# Sheet1.net
KiCad netlist of a schematic drawn in Altium Designer
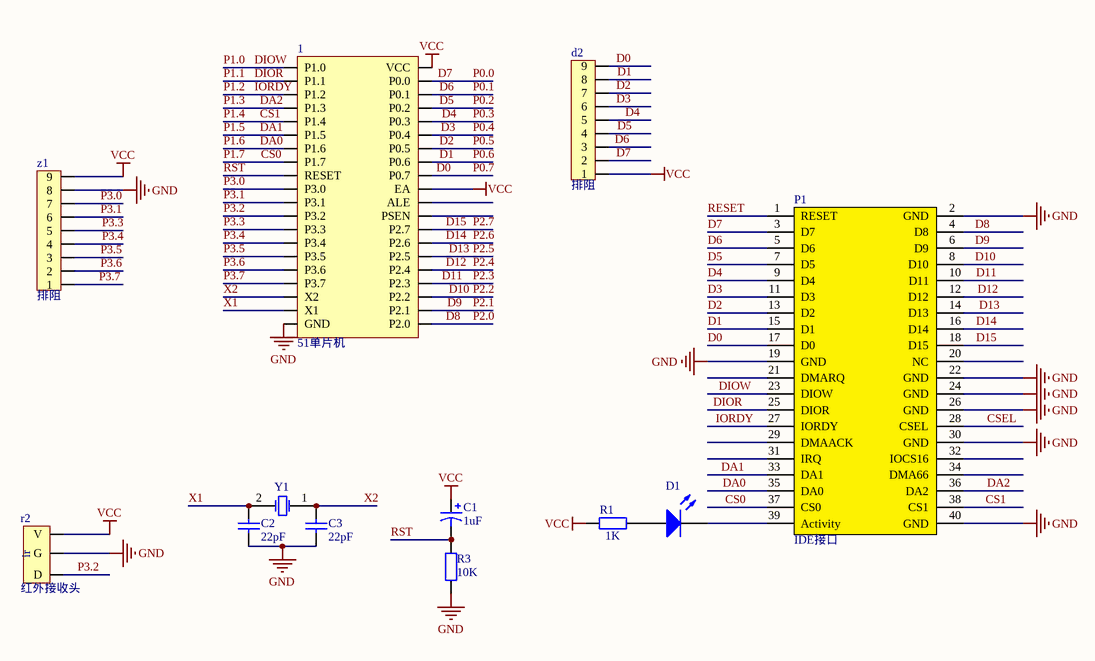
[diagram p0: Sheet1.SchDoc]

(export (version "E")
  (design (tool "Eeschema 10.0.6"))
  (components
    (comp (ref "1") (value "51单片机") (footprint "51单片机") (libsource (lib "原理图库") (part "51单片机")))
    (comp (ref "C1")
      (value "1uF")
      (footprint "电解电容")
      (description "Polarized Capacitor (Radial)")
      (fields (field (name "Comment") "Cap Pol1") (field (name "PUBLISHER") "Altium Limited"))
      (libsource (lib "系统自带集成库") (part "Cap Pol1"))
    )
    (comp (ref "C2")
      (value "22pF")
      (footprint "无极电容")
      (description "Capacitor")
      (fields (field (name "Comment") "Cap") (field (name "PUBLISHER") "Altium Limited"))
      (libsource (lib "系统自带集成库") (part "Cap"))
    )
    (comp (ref "C3")
      (value "22pF")
      (footprint "无极电容")
      (description "Capacitor")
      (fields (field (name "Comment") "Cap") (field (name "PUBLISHER") "Altium Limited"))
      (libsource (lib "系统自带集成库") (part "Cap"))
    )
    (comp (ref "D1")
      (value "LED0")
      (footprint "LED")
      (description "Typical INFRARED GaAs LED")
      (fields (field (name "PUBLISHER") "Altium Limited"))
      (libsource (lib "Miscellaneous Devices") (part "LED0"))
    )
    (comp (ref "d2") (value "排阻") (footprint "排阻") (libsource (lib "原理图库") (part "排阻")))
    (comp (ref "P1") (value "IDE接口") (footprint "IDE接口封装40PIN") (libsource (lib "原理图库") (part "IDE接口")))
    (comp (ref "R1")
      (value "1K")
      (footprint "电阻")
      (description "Resistor")
      (fields (field (name "Comment") "Res2") (field (name "PUBLISHER") "Altium Limited"))
      (libsource (lib "Miscellaneous Devices") (part "Res2"))
    )
    (comp (ref "r2") (value "红外接收头") (footprint "IR红外接收头") (libsource (lib "原理图库") (part "红外接收头")))
    (comp (ref "R3")
      (value "10K")
      (footprint "电阻")
      (description "Resistor")
      (fields (field (name "Comment") "Res2") (field (name "PUBLISHER") "Altium Limited"))
      (libsource (lib "系统自带集成库") (part "Res2"))
    )
    (comp (ref "Y1")
      (value "XTAL")
      (footprint "晶振")
      (description "Crystal Oscillator")
      (fields (field (name "PUBLISHER") "Altium Limited"))
      (libsource (lib "系统自带集成库") (part "XTAL"))
    )
    (comp (ref "z1") (value "排阻") (footprint "排阻") (libsource (lib "原理图库") (part "排阻")))
  )
  (nets
    (net (code "1") (name "/CS0") (class "Default")
      (node (ref "1") (pin "8") (pinfunction "P1.7_8") (pintype "passive"))
      (node (ref "P1") (pin "37") (pinfunction "CS0_37") (pintype "passive"))
    )
    (net (code "2") (name "/CS1") (class "Default")
      (node (ref "1") (pin "5") (pinfunction "P1.4_5") (pintype "passive"))
      (node (ref "P1") (pin "38") (pinfunction "CS1_38") (pintype "passive"))
    )
    (net (code "3") (name "/CSEL") (class "Default")
      (node (ref "P1") (pin "28") (pinfunction "CSEL_28") (pintype "passive"))
    )
    (net (code "4") (name "/D0") (class "Default")
      (node (ref "1") (pin "32") (pinfunction "P0.7_32") (pintype "passive"))
      (node (ref "P1") (pin "17") (pinfunction "D0_17") (pintype "passive"))
      (node (ref "d2") (pin "9") (pinfunction "9_9") (pintype "passive"))
    )
    (net (code "5") (name "/D1") (class "Default")
      (node (ref "1") (pin "33") (pinfunction "P0.6_33") (pintype "passive"))
      (node (ref "P1") (pin "15") (pinfunction "D1_15") (pintype "passive"))
      (node (ref "d2") (pin "8") (pinfunction "8_8") (pintype "passive"))
    )
    (net (code "6") (name "/D2") (class "Default")
      (node (ref "1") (pin "34") (pinfunction "P0.5_34") (pintype "passive"))
      (node (ref "P1") (pin "13") (pinfunction "D2_13") (pintype "passive"))
      (node (ref "d2") (pin "7") (pinfunction "7_7") (pintype "passive"))
    )
    (net (code "7") (name "/D3") (class "Default")
      (node (ref "1") (pin "35") (pinfunction "P0.4_35") (pintype "passive"))
      (node (ref "P1") (pin "11") (pinfunction "D3_11") (pintype "passive"))
      (node (ref "d2") (pin "6") (pinfunction "6_6") (pintype "passive"))
    )
    (net (code "8") (name "/D4") (class "Default")
      (node (ref "1") (pin "36") (pinfunction "P0.3_36") (pintype "passive"))
      (node (ref "P1") (pin "9") (pinfunction "D4_9") (pintype "passive"))
      (node (ref "d2") (pin "5") (pinfunction "5_5") (pintype "passive"))
    )
    (net (code "9") (name "/D5") (class "Default")
      (node (ref "1") (pin "37") (pinfunction "P0.2_37") (pintype "passive"))
      (node (ref "P1") (pin "7") (pinfunction "D5_7") (pintype "passive"))
      (node (ref "d2") (pin "4") (pinfunction "4_4") (pintype "passive"))
    )
    (net (code "10") (name "/D6") (class "Default")
      (node (ref "1") (pin "38") (pinfunction "P0.1_38") (pintype "passive"))
      (node (ref "P1") (pin "5") (pinfunction "D6_5") (pintype "passive"))
      (node (ref "d2") (pin "3") (pinfunction "3_3") (pintype "passive"))
    )
    (net (code "11") (name "/D7") (class "Default")
      (node (ref "1") (pin "39") (pinfunction "P0.0_39") (pintype "passive"))
      (node (ref "P1") (pin "3") (pinfunction "D7_3") (pintype "passive"))
      (node (ref "d2") (pin "2") (pinfunction "2_2") (pintype "passive"))
    )
    (net (code "12") (name "/D8") (class "Default")
      (node (ref "1") (pin "21") (pinfunction "P2.0_21") (pintype "passive"))
      (node (ref "P1") (pin "4") (pinfunction "D8_4") (pintype "passive"))
    )
    (net (code "13") (name "/D9") (class "Default")
      (node (ref "1") (pin "22") (pinfunction "P2.1_22") (pintype "passive"))
      (node (ref "P1") (pin "6") (pinfunction "D9_6") (pintype "passive"))
    )
    (net (code "14") (name "/D10") (class "Default")
      (node (ref "1") (pin "23") (pinfunction "P2.2_23") (pintype "passive"))
      (node (ref "P1") (pin "8") (pinfunction "D10_8") (pintype "passive"))
    )
    (net (code "15") (name "/D11") (class "Default")
      (node (ref "1") (pin "24") (pinfunction "P2.3_24") (pintype "passive"))
      (node (ref "P1") (pin "10") (pinfunction "D11_10") (pintype "passive"))
    )
    (net (code "16") (name "/D12") (class "Default")
      (node (ref "1") (pin "25") (pinfunction "P2.4_25") (pintype "passive"))
      (node (ref "P1") (pin "12") (pinfunction "D12_12") (pintype "passive"))
    )
    (net (code "17") (name "/D13") (class "Default")
      (node (ref "1") (pin "26") (pinfunction "P2.5_26") (pintype "passive"))
      (node (ref "P1") (pin "14") (pinfunction "D13_14") (pintype "passive"))
    )
    (net (code "18") (name "/D14") (class "Default")
      (node (ref "1") (pin "27") (pinfunction "P2.6_27") (pintype "passive"))
      (node (ref "P1") (pin "16") (pinfunction "D14_16") (pintype "passive"))
    )
    (net (code "19") (name "/D15") (class "Default")
      (node (ref "1") (pin "28") (pinfunction "P2.7_28") (pintype "passive"))
      (node (ref "P1") (pin "18") (pinfunction "D15_18") (pintype "passive"))
    )
    (net (code "20") (name "/DA0") (class "Default")
      (node (ref "1") (pin "7") (pinfunction "P1.6_7") (pintype "passive"))
      (node (ref "P1") (pin "35") (pinfunction "DA0_35") (pintype "passive"))
    )
    (net (code "21") (name "/DA1") (class "Default")
      (node (ref "1") (pin "6") (pinfunction "P1.5_6") (pintype "passive"))
      (node (ref "P1") (pin "33") (pinfunction "DA1_33") (pintype "passive"))
    )
    (net (code "22") (name "/DA2") (class "Default")
      (node (ref "1") (pin "4") (pinfunction "P1.3_4") (pintype "passive"))
      (node (ref "P1") (pin "36") (pinfunction "DA2_36") (pintype "passive"))
    )
    (net (code "23") (name "/DIOR") (class "Default")
      (node (ref "1") (pin "2") (pinfunction "P1.1_2") (pintype "passive"))
      (node (ref "P1") (pin "25") (pinfunction "DIOR_25") (pintype "passive"))
    )
    (net (code "24") (name "/DIOW") (class "Default")
      (node (ref "1") (pin "1") (pinfunction "P1.0_1") (pintype "passive"))
      (node (ref "P1") (pin "23") (pinfunction "DIOW_23") (pintype "passive"))
    )
    (net (code "25") (name "/IORDY") (class "Default")
      (node (ref "1") (pin "3") (pinfunction "P1.2_3") (pintype "passive"))
      (node (ref "P1") (pin "27") (pinfunction "IORDY_27") (pintype "passive"))
    )
    (net (code "26") (name "/P3.0") (class "Default")
      (node (ref "1") (pin "10") (pinfunction "P3.0_10") (pintype "passive"))
      (node (ref "z1") (pin "7") (pinfunction "7_7") (pintype "passive"))
    )
    (net (code "27") (name "/P3.1") (class "Default")
      (node (ref "1") (pin "11") (pinfunction "P3.1_11") (pintype "passive"))
      (node (ref "z1") (pin "6") (pinfunction "6_6") (pintype "passive"))
    )
    (net (code "28") (name "/P3.2") (class "Default")
      (node (ref "1") (pin "12") (pinfunction "P3.2_12") (pintype "passive"))
      (node (ref "r2") (pin "1") (pinfunction "D_1") (pintype "passive"))
    )
    (net (code "29") (name "/P3.3") (class "Default")
      (node (ref "1") (pin "13") (pinfunction "P3.3_13") (pintype "passive"))
      (node (ref "z1") (pin "5") (pinfunction "5_5") (pintype "passive"))
    )
    (net (code "30") (name "/P3.4") (class "Default")
      (node (ref "1") (pin "14") (pinfunction "P3.4_14") (pintype "passive"))
      (node (ref "z1") (pin "4") (pinfunction "4_4") (pintype "passive"))
    )
    (net (code "31") (name "/P3.5") (class "Default")
      (node (ref "1") (pin "15") (pinfunction "P3.5_15") (pintype "passive"))
      (node (ref "z1") (pin "3") (pinfunction "3_3") (pintype "passive"))
    )
    (net (code "32") (name "/P3.6") (class "Default")
      (node (ref "1") (pin "16") (pinfunction "P3.6_16") (pintype "passive"))
      (node (ref "z1") (pin "2") (pinfunction "2_2") (pintype "passive"))
    )
    (net (code "33") (name "/P3.7") (class "Default")
      (node (ref "1") (pin "17") (pinfunction "P3.7_17") (pintype "passive"))
      (node (ref "z1") (pin "1") (pinfunction "1_1") (pintype "passive"))
    )
    (net (code "34") (name "/RESET") (class "Default")
      (node (ref "P1") (pin "1") (pinfunction "RESET_1") (pintype "passive"))
    )
    (net (code "35") (name "/RST") (class "Default")
      (node (ref "1") (pin "9") (pinfunction "RESET_9") (pintype "passive"))
      (node (ref "C1") (pin "2") (pinfunction "2_2") (pintype "passive"))
      (node (ref "R3") (pin "1") (pinfunction "1_1") (pintype "passive"))
    )
    (net (code "36") (name "/X1") (class "Default")
      (node (ref "1") (pin "19") (pinfunction "X1_19") (pintype "passive"))
      (node (ref "C2") (pin "2") (pinfunction "2_2") (pintype "passive"))
      (node (ref "Y1") (pin "2") (pinfunction "OSC2_2") (pintype "passive"))
    )
    (net (code "37") (name "/X2") (class "Default")
      (node (ref "1") (pin "18") (pinfunction "X2_18") (pintype "passive"))
      (node (ref "C3") (pin "1") (pinfunction "1_1") (pintype "passive"))
      (node (ref "Y1") (pin "1") (pinfunction "OSC1_1") (pintype "passive"))
    )
    (net (code "38") (name "GND") (class "Default")
      (node (ref "1") (pin "20") (pinfunction "GND_20") (pintype "passive"))
      (node (ref "C2") (pin "1") (pinfunction "1_1") (pintype "passive"))
      (node (ref "C3") (pin "2") (pinfunction "2_2") (pintype "passive"))
      (node (ref "P1") (pin "19") (pinfunction "GND_19") (pintype "passive"))
      (node (ref "P1") (pin "2") (pinfunction "GND_2") (pintype "passive"))
      (node (ref "P1") (pin "22") (pinfunction "GND_22") (pintype "passive"))
      (node (ref "P1") (pin "24") (pinfunction "GND_24") (pintype "passive"))
      (node (ref "P1") (pin "26") (pinfunction "GND_26") (pintype "passive"))
      (node (ref "P1") (pin "30") (pinfunction "GND_30") (pintype "passive"))
      (node (ref "P1") (pin "40") (pinfunction "GND_40") (pintype "passive"))
      (node (ref "R3") (pin "2") (pinfunction "2_2") (pintype "passive"))
      (node (ref "r2") (pin "2") (pinfunction "G_2") (pintype "passive"))
      (node (ref "z1") (pin "8") (pinfunction "8_8") (pintype "passive"))
    )
    (net (code "39") (name "Net-(D1-A)") (class "Default")
      (node (ref "D1") (pin "1") (pinfunction "A_1") (pintype "passive"))
      (node (ref "R1") (pin "2") (pinfunction "2_2") (pintype "passive"))
    )
    (net (code "40") (name "Net-(D1-K)") (class "Default")
      (node (ref "D1") (pin "2") (pinfunction "K_2") (pintype "passive"))
      (node (ref "P1") (pin "39") (pinfunction "Activity_39") (pintype "passive"))
    )
    (net (code "41") (name "VCC") (class "Default")
      (node (ref "1") (pin "31") (pinfunction "EA_31") (pintype "passive"))
      (node (ref "1") (pin "40") (pinfunction "VCC_40") (pintype "passive"))
      (node (ref "C1") (pin "1") (pinfunction "1_1") (pintype "passive"))
      (node (ref "R1") (pin "1") (pinfunction "1_1") (pintype "passive"))
      (node (ref "d2") (pin "1") (pinfunction "1_1") (pintype "passive"))
      (node (ref "r2") (pin "3") (pinfunction "V_3") (pintype "passive"))
      (node (ref "z1") (pin "9") (pinfunction "9_9") (pintype "passive"))
    )
    (net (code "42") (name "unconnected-(1-ALE-Pad30)") (class "Default")
      (node (ref "1") (pin "30") (pinfunction "ALE_30") (pintype "passive"))
    )
    (net (code "43") (name "unconnected-(1-PSEN-Pad29)") (class "Default")
      (node (ref "1") (pin "29") (pinfunction "PSEN_29") (pintype "passive"))
    )
    (net (code "44") (name "unconnected-(P1-DMA66-Pad34)") (class "Default")
      (node (ref "P1") (pin "34") (pinfunction "DMA66_34") (pintype "passive"))
    )
    (net (code "45") (name "unconnected-(P1-DMAACK-Pad29)") (class "Default")
      (node (ref "P1") (pin "29") (pinfunction "DMAACK_29") (pintype "passive"))
    )
    (net (code "46") (name "unconnected-(P1-DMARQ-Pad21)") (class "Default")
      (node (ref "P1") (pin "21") (pinfunction "DMARQ_21") (pintype "passive"))
    )
    (net (code "47") (name "unconnected-(P1-IOCS16-Pad32)") (class "Default")
      (node (ref "P1") (pin "32") (pinfunction "IOCS16_32") (pintype "passive"))
    )
    (net (code "48") (name "unconnected-(P1-IRQ-Pad31)") (class "Default")
      (node (ref "P1") (pin "31") (pinfunction "IRQ_31") (pintype "passive"))
    )
    (net (code "49") (name "unconnected-(P1-NC-Pad20)") (class "Default")
      (node (ref "P1") (pin "20") (pinfunction "NC_20") (pintype "passive"))
    )
  )
)
